# SENSORS.net
KiCad netlist of a schematic drawn in Altium Designer
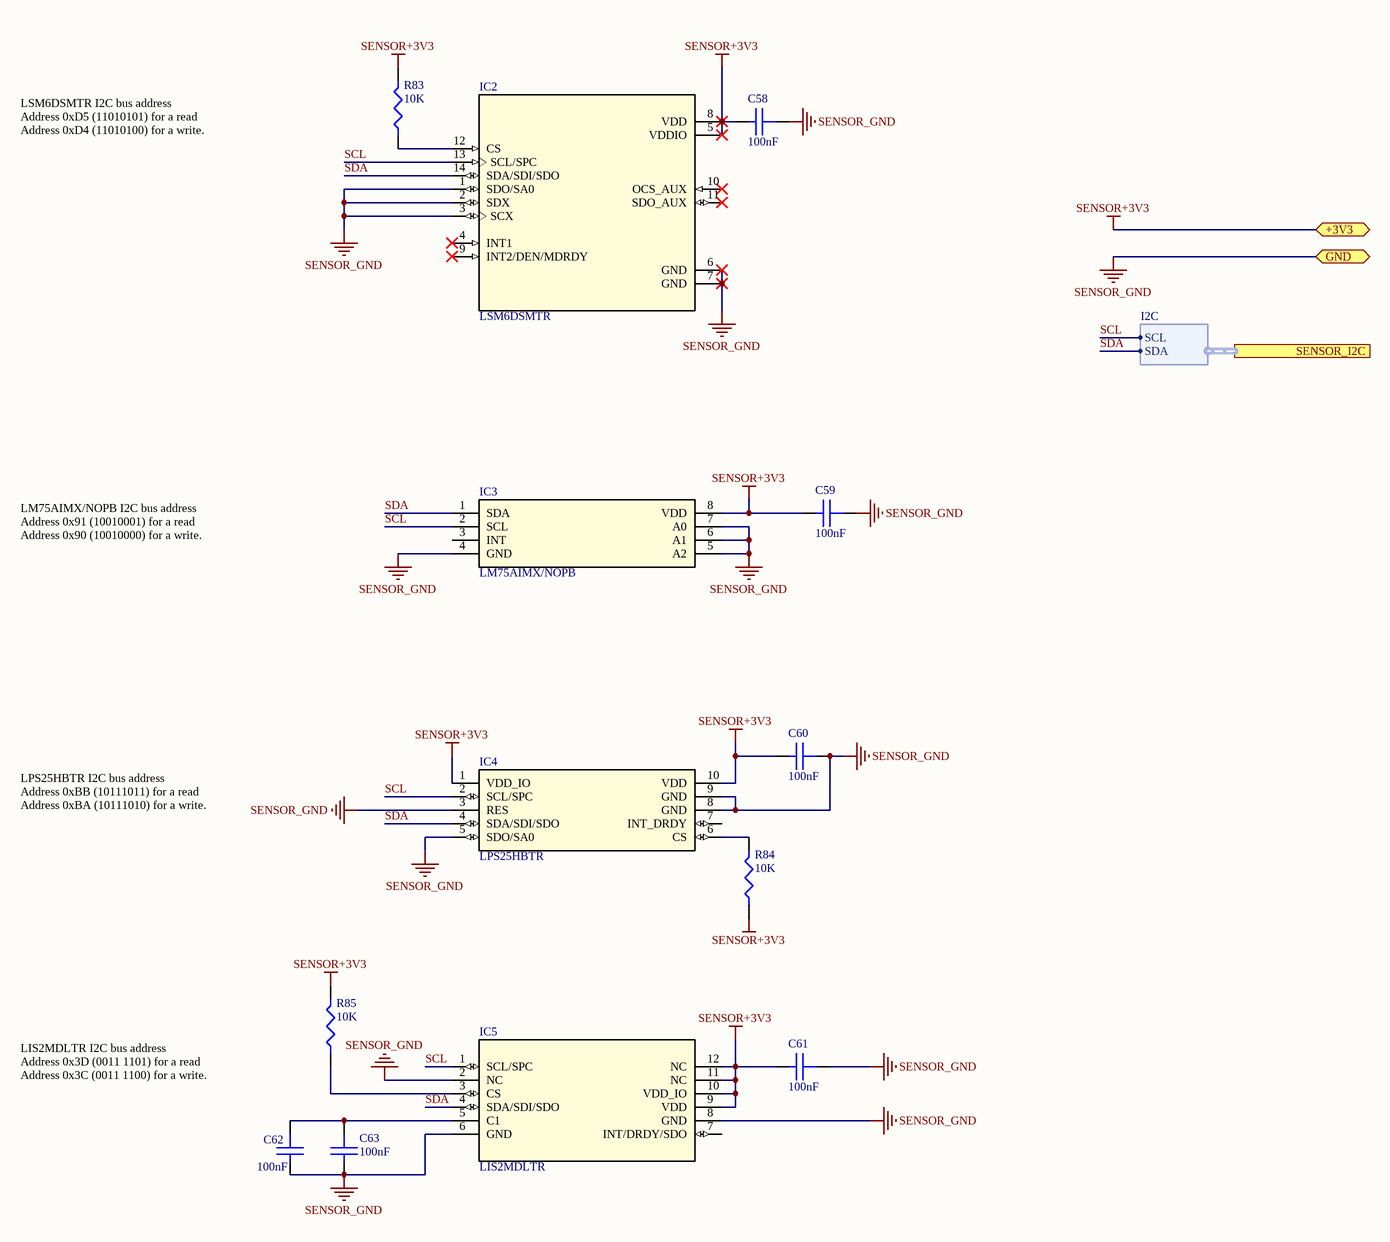
[diagram p0: SENSORS.SchDoc]

(export (version "E")
  (design (tool "Eeschema 10.0.6"))
  (components
    (comp (ref "C58")
      (value "100nF")
      (footprint "C0603")
      (description "100nF, 25V, X7R, 10%, 0603")
      (fields
        (field (name "MANUFACTURER") "Yageo")
        (field (name "MANUFACTURER PART NUMBER") "CC0603KRX7R8BB104")
      )
      (libsource (lib "McmLibrary") (part "CC0603KRX7R8BB104"))
    )
    (comp (ref "C59")
      (value "100nF")
      (footprint "C0603")
      (description "100nF, 25V, X7R, 10%, 0603")
      (fields
        (field (name "MANUFACTURER") "Yageo")
        (field (name "MANUFACTURER PART NUMBER") "CC0603KRX7R8BB104")
      )
      (libsource (lib "McmLibrary") (part "CC0603KRX7R8BB104"))
    )
    (comp (ref "C60")
      (value "100nF")
      (footprint "C0603")
      (description "100nF, 25V, X7R, 10%, 0603")
      (fields
        (field (name "MANUFACTURER") "Yageo")
        (field (name "MANUFACTURER PART NUMBER") "CC0603KRX7R8BB104")
      )
      (libsource (lib "McmLibrary") (part "CC0603KRX7R8BB104"))
    )
    (comp (ref "C61")
      (value "100nF")
      (footprint "C0603")
      (description "100nF, 25V, X7R, 10%, 0603")
      (fields
        (field (name "MANUFACTURER") "Yageo")
        (field (name "MANUFACTURER PART NUMBER") "CC0603KRX7R8BB104")
      )
      (libsource (lib "McmLibrary") (part "CC0603KRX7R8BB104"))
    )
    (comp (ref "C62")
      (value "100nF")
      (footprint "C0603")
      (description "100nF, 25V, X7R, 10%, 0603")
      (fields
        (field (name "MANUFACTURER") "Yageo")
        (field (name "MANUFACTURER PART NUMBER") "CC0603KRX7R8BB104")
      )
      (libsource (lib "McmLibrary") (part "CC0603KRX7R8BB104"))
    )
    (comp (ref "C63")
      (value "100nF")
      (footprint "C0603")
      (description "100nF, 25V, X7R, 10%, 0603")
      (fields
        (field (name "MANUFACTURER") "Yageo")
        (field (name "MANUFACTURER PART NUMBER") "CC0603KRX7R8BB104")
      )
      (libsource (lib "McmLibrary") (part "CC0603KRX7R8BB104"))
    )
    (comp (ref "IC2")
      (value "LSM6DSMTR")
      (footprint "PQFN50P300X250X86-14N")
      (description "IMU ACCEL/GYRO I2C/SPI 14LGA")
      (fields (field (name "MANUFACTURER") "STMicroelectronics"))
      (libsource (lib "Sensors") (part "LSM6DSMTR"))
    )
    (comp (ref "IC3")
      (value "LM75AIMX/NOPB")
      (footprint "SO08")
      (description "SENSOR DIGITAL -55C-125C 8SOIC")
      (fields (field (name "MANUFACTURER") "TI National Semiconductor"))
      (libsource (lib "Sensors") (part "LM75AIMX/NOPB"))
    )
    (comp (ref "IC4")
      (value "LPS25HBTR")
      (footprint "HLGA10_2P5X2P5")
      (description "IC MEMS PRESSURE SENSOR 10HCLGA")
      (fields (field (name "MANUFACTURER") "STMicroelectronics"))
      (libsource (lib "Sensors") (part "LPS25HBTR"))
    )
    (comp (ref "IC5")
      (value "LIS2MDLTR")
      (footprint "LGA12")
      (description "ULTRA-COMPACT HIGH-PERFORMANCE E")
      (fields (field (name "MANUFACTURER") "STMicroelectronics"))
      (libsource (lib "Sensors") (part "LIS2MDLTR"))
    )
    (comp (ref "R83")
      (value "10K")
      (footprint "R0603")
      (description "10K OHM 1% 1/10W 0603")
      (fields
        (field (name "MANUFACTURER") "Yageo")
        (field (name "MANUFACTURER PART NUMBER") "RT0603FRE0710KL")
      )
      (libsource (lib "McmLibrary") (part "RT0603FRE0710KL"))
    )
    (comp (ref "R84")
      (value "10K")
      (footprint "R0603")
      (description "10K OHM 1% 1/10W 0603")
      (fields
        (field (name "MANUFACTURER") "Yageo")
        (field (name "MANUFACTURER PART NUMBER") "RT0603FRE0710KL")
      )
      (libsource (lib "McmLibrary") (part "RT0603FRE0710KL"))
    )
    (comp (ref "R85")
      (value "10K")
      (footprint "R0603")
      (description "10K OHM 1% 1/10W 0603")
      (fields
        (field (name "MANUFACTURER") "Yageo")
        (field (name "MANUFACTURER PART NUMBER") "RT0603FRE0710KL")
      )
      (libsource (lib "McmLibrary") (part "RT0603FRE0710KL"))
    )
  )
  (nets
    (net (code "3") (name "/SCL") (class "Default")
      (node (ref "IC2") (pin "13") (pinfunction "SCL/SPC_13") (pintype "input"))
      (node (ref "IC3") (pin "2") (pinfunction "SCL_2") (pintype "passive"))
      (node (ref "IC4") (pin "2") (pinfunction "SCL/SPC_2") (pintype "bidirectional"))
      (node (ref "IC5") (pin "1") (pinfunction "SCL/SPC_1") (pintype "bidirectional"))
    )
    (net (code "4") (name "/SDA") (class "Default")
      (node (ref "IC2") (pin "14") (pinfunction "SDA/SDI/SDO_14") (pintype "bidirectional"))
      (node (ref "IC3") (pin "1") (pinfunction "SDA_1") (pintype "passive"))
      (node (ref "IC4") (pin "4") (pinfunction "SDA/SDI/SDO_4") (pintype "bidirectional"))
      (node (ref "IC5") (pin "4") (pinfunction "SDA/SDI/SDO_4") (pintype "bidirectional"))
    )
    (net (code "6") (name "Net-(IC2-CS)") (class "Default")
      (node (ref "IC2") (pin "12") (pinfunction "CS_12") (pintype "input"))
      (node (ref "R83") (pin "1") (pinfunction "1_1") (pintype "passive"))
    )
    (net (code "7") (name "Net-(IC4-CS)") (class "Default")
      (node (ref "IC4") (pin "6") (pinfunction "CS_6") (pintype "bidirectional"))
      (node (ref "R84") (pin "2") (pinfunction "2_2") (pintype "passive"))
    )
    (net (code "8") (name "Net-(IC5-C1)") (class "Default")
      (node (ref "C62") (pin "2") (pintype "passive"))
      (node (ref "C63") (pin "2") (pintype "passive"))
      (node (ref "IC5") (pin "5") (pinfunction "C1_5") (pintype "passive"))
    )
    (net (code "9") (name "Net-(IC5-CS)") (class "Default")
      (node (ref "IC5") (pin "3") (pinfunction "CS_3") (pintype "bidirectional"))
      (node (ref "R85") (pin "1") (pinfunction "1_1") (pintype "passive"))
    )
    (net (code "10") (name "SENSOR+3V3") (class "Default")
      (node (ref "C58") (pin "1") (pintype "passive"))
      (node (ref "C59") (pin "1") (pintype "passive"))
      (node (ref "C60") (pin "1") (pintype "passive"))
      (node (ref "C61") (pin "1") (pintype "passive"))
      (node (ref "IC2") (pin "5") (pinfunction "VDDIO_5") (pintype "power_in"))
      (node (ref "IC2") (pin "8") (pinfunction "VDD_8") (pintype "power_in"))
      (node (ref "IC3") (pin "8") (pinfunction "VDD_8") (pintype "passive"))
      (node (ref "IC4") (pin "1") (pinfunction "VDD_IO_1") (pintype "power_in"))
      (node (ref "IC4") (pin "10") (pinfunction "VDD_10") (pintype "power_in"))
      (node (ref "IC5") (pin "10") (pinfunction "VDD_IO_10") (pintype "power_in"))
      (node (ref "IC5") (pin "11") (pinfunction "NC_11") (pintype "passive"))
      (node (ref "IC5") (pin "12") (pinfunction "NC_12") (pintype "passive"))
      (node (ref "IC5") (pin "9") (pinfunction "VDD_9") (pintype "power_in"))
      (node (ref "R83") (pin "2") (pinfunction "2_2") (pintype "passive"))
      (node (ref "R84") (pin "1") (pinfunction "1_1") (pintype "passive"))
      (node (ref "R85") (pin "2") (pinfunction "2_2") (pintype "passive"))
    )
    (net (code "11") (name "SENSOR_GND") (class "Default")
      (node (ref "C58") (pin "2") (pintype "passive"))
      (node (ref "C59") (pin "2") (pintype "passive"))
      (node (ref "C60") (pin "2") (pintype "passive"))
      (node (ref "C61") (pin "2") (pintype "passive"))
      (node (ref "C62") (pin "1") (pintype "passive"))
      (node (ref "C63") (pin "1") (pintype "passive"))
      (node (ref "IC2") (pin "1") (pinfunction "SDO/SA0_1") (pintype "bidirectional"))
      (node (ref "IC2") (pin "2") (pinfunction "SDX_2") (pintype "bidirectional"))
      (node (ref "IC2") (pin "3") (pinfunction "SCX_3") (pintype "bidirectional"))
      (node (ref "IC2") (pin "6") (pinfunction "GND_6") (pintype "power_in"))
      (node (ref "IC2") (pin "7") (pinfunction "GND_7") (pintype "power_in"))
      (node (ref "IC3") (pin "4") (pinfunction "GND_4") (pintype "passive"))
      (node (ref "IC3") (pin "5") (pinfunction "A2_5") (pintype "passive"))
      (node (ref "IC3") (pin "6") (pinfunction "A1_6") (pintype "passive"))
      (node (ref "IC3") (pin "7") (pinfunction "A0_7") (pintype "passive"))
      (node (ref "IC4") (pin "3") (pinfunction "RES_3") (pintype "passive"))
      (node (ref "IC4") (pin "5") (pinfunction "SDO/SA0_5") (pintype "bidirectional"))
      (node (ref "IC4") (pin "8") (pinfunction "GND_8") (pintype "power_in"))
      (node (ref "IC4") (pin "9") (pinfunction "GND_9") (pintype "power_in"))
      (node (ref "IC5") (pin "2") (pinfunction "NC_2") (pintype "passive"))
      (node (ref "IC5") (pin "6") (pinfunction "GND_6") (pintype "power_in"))
      (node (ref "IC5") (pin "8") (pinfunction "GND_8") (pintype "power_in"))
    )
    (net (code "12") (name "unconnected-(IC2-INT1-Pad4)") (class "Default")
      (node (ref "IC2") (pin "4") (pinfunction "INT1_4") (pintype "input+no_connect"))
    )
    (net (code "13") (name "unconnected-(IC2-INT2{slash}DEN{slash}MDRDY-Pad9)") (class "Default")
      (node (ref "IC2") (pin "9") (pinfunction "INT2/DEN/MDRDY_9") (pintype "input+no_connect"))
    )
    (net (code "14") (name "unconnected-(IC2-OCS_AUX-Pad10)") (class "Default")
      (node (ref "IC2") (pin "10") (pinfunction "OCS_AUX_10") (pintype "input+no_connect"))
    )
    (net (code "15") (name "unconnected-(IC2-SDO_AUX-Pad11)") (class "Default")
      (node (ref "IC2") (pin "11") (pinfunction "SDO_AUX_11") (pintype "bidirectional+no_connect"))
    )
    (net (code "16") (name "unconnected-(IC3-INT-Pad3)") (class "Default")
      (node (ref "IC3") (pin "3") (pinfunction "INT_3") (pintype "passive"))
    )
    (net (code "17") (name "unconnected-(IC4-INT_DRDY-Pad7)") (class "Default")
      (node (ref "IC4") (pin "7") (pinfunction "INT_DRDY_7") (pintype "bidirectional"))
    )
    (net (code "18") (name "unconnected-(IC5-INT{slash}DRDY{slash}SDO-Pad7)") (class "Default")
      (node (ref "IC5") (pin "7") (pinfunction "INT/DRDY/SDO_7") (pintype "bidirectional"))
    )
  )
)
